# adc.net
KiCad netlist of a schematic drawn in Altium Designer
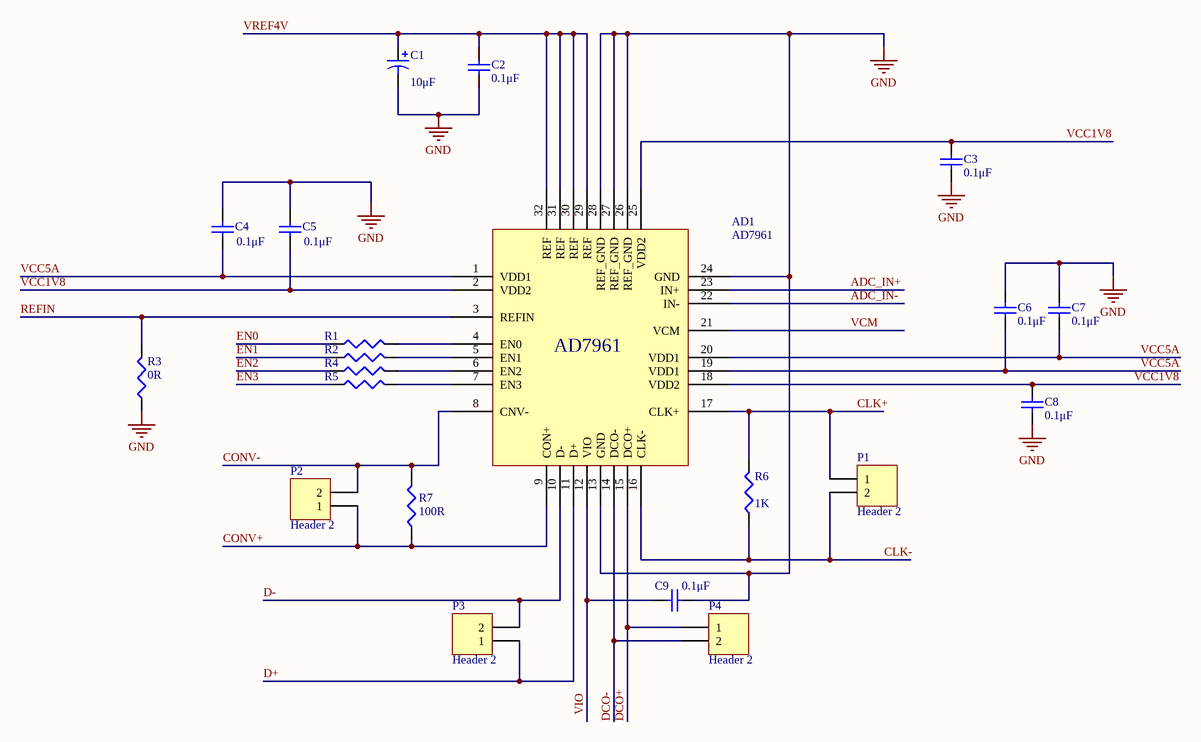
[diagram p0: adc.SchDoc]

(export (version "E")
  (design (tool "Eeschema 10.0.6"))
  (components
    (comp (ref "AD1")
      (value "AD7961")
      (footprint "QFN50P500X500X80-33N")
      (libsource (lib "nir_usb") (part "AD7961"))
    )
    (comp (ref "C1")
      (value "10μF")
      (footprint "C0805")
      (description "Polarized Capacitor (Surface Mount)")
      (fields (field (name "Comment") "Cap Pol3") (field (name "PUBLISHER") "Altium Limited"))
      (libsource (lib "Miscellaneous Devices") (part "Cap Pol3"))
    )
    (comp (ref "C2")
      (value "0.1μF")
      (footprint "1608[0603]")
      (description "Capacitor (Semiconductor SIM Model)")
      (fields (field (name "Comment") "Cap Semi") (field (name "PUBLISHER") "Altium Limited"))
      (libsource (lib "Miscellaneous Devices") (part "Cap Semi"))
    )
    (comp (ref "C3")
      (value "0.1μF")
      (footprint "1608[0603]")
      (description "Capacitor (Semiconductor SIM Model)")
      (fields (field (name "Comment") "Cap Semi") (field (name "PUBLISHER") "Altium Limited"))
      (libsource (lib "Miscellaneous Devices") (part "Cap Semi"))
    )
    (comp (ref "C4")
      (value "0.1μF")
      (footprint "1608[0603]")
      (description "Capacitor (Semiconductor SIM Model)")
      (fields (field (name "Comment") "Cap Semi") (field (name "PUBLISHER") "Altium Limited"))
      (libsource (lib "Miscellaneous Devices") (part "Cap Semi"))
    )
    (comp (ref "C5")
      (value "0.1μF")
      (footprint "1608[0603]")
      (description "Capacitor (Semiconductor SIM Model)")
      (fields (field (name "Comment") "Cap Semi") (field (name "PUBLISHER") "Altium Limited"))
      (libsource (lib "Miscellaneous Devices") (part "Cap Semi"))
    )
    (comp (ref "C6")
      (value "0.1μF")
      (footprint "1608[0603]")
      (description "Capacitor (Semiconductor SIM Model)")
      (fields (field (name "Comment") "Cap Semi") (field (name "PUBLISHER") "Altium Limited"))
      (libsource (lib "Miscellaneous Devices") (part "Cap Semi"))
    )
    (comp (ref "C7")
      (value "0.1μF")
      (footprint "1608[0603]")
      (description "Capacitor (Semiconductor SIM Model)")
      (fields (field (name "Comment") "Cap Semi") (field (name "PUBLISHER") "Altium Limited"))
      (libsource (lib "Miscellaneous Devices") (part "Cap Semi"))
    )
    (comp (ref "C8")
      (value "0.1μF")
      (footprint "1608[0603]")
      (description "Capacitor (Semiconductor SIM Model)")
      (fields (field (name "Comment") "Cap Semi") (field (name "PUBLISHER") "Altium Limited"))
      (libsource (lib "Miscellaneous Devices") (part "Cap Semi"))
    )
    (comp (ref "C9")
      (value "0.1μF")
      (footprint "1608[0603]")
      (description "Capacitor (Semiconductor SIM Model)")
      (fields (field (name "Comment") "Cap Semi") (field (name "PUBLISHER") "Altium Limited"))
      (libsource (lib "Miscellaneous Devices") (part "Cap Semi"))
    )
    (comp (ref "P1")
      (value "Header 2")
      (footprint "HDR1X2")
      (description "Header, 2-Pin")
      (fields (field (name "PUBLISHER") "Altium Limited"))
      (libsource (lib "Miscellaneous Connectors") (part "Header 2"))
    )
    (comp (ref "P2")
      (value "Header 2")
      (footprint "HDR1X2")
      (description "Header, 2-Pin")
      (fields (field (name "PUBLISHER") "Altium Limited"))
      (libsource (lib "") (part "Header 2_1"))
    )
    (comp (ref "P3")
      (value "Header 2")
      (footprint "HDR1X2")
      (description "Header, 2-Pin")
      (fields (field (name "PUBLISHER") "Altium Limited"))
      (libsource (lib "") (part "Header 2_1"))
    )
    (comp (ref "P4")
      (value "Header 2")
      (footprint "HDR1X2")
      (description "Header, 2-Pin")
      (fields (field (name "PUBLISHER") "Altium Limited"))
      (libsource (lib "Miscellaneous Connectors") (part "Header 2"))
    )
    (comp (ref "R1")
      (value "Res3")
      (footprint "J1-0603")
      (description "Resistor")
      (fields (field (name "PUBLISHER") "Altium Limited"))
      (libsource (lib "Miscellaneous Devices") (part "Res3"))
    )
    (comp (ref "R2")
      (value "Res3")
      (footprint "J1-0603")
      (description "Resistor")
      (fields (field (name "PUBLISHER") "Altium Limited"))
      (libsource (lib "Miscellaneous Devices") (part "Res3"))
    )
    (comp (ref "R3")
      (value "0R")
      (footprint "J1-0603")
      (description "Resistor")
      (fields (field (name "PUBLISHER") "Altium Limited"))
      (libsource (lib "Miscellaneous Devices") (part "Res3"))
    )
    (comp (ref "R4")
      (value "Res3")
      (footprint "J1-0603")
      (description "Resistor")
      (fields (field (name "PUBLISHER") "Altium Limited"))
      (libsource (lib "Miscellaneous Devices") (part "Res3"))
    )
    (comp (ref "R5")
      (value "Res3")
      (footprint "J1-0603")
      (description "Resistor")
      (fields (field (name "PUBLISHER") "Altium Limited"))
      (libsource (lib "Miscellaneous Devices") (part "Res3"))
    )
    (comp (ref "R6")
      (value "1K")
      (footprint "J1-0603")
      (description "Resistor")
      (fields (field (name "Comment") "Res3") (field (name "PUBLISHER") "Altium Limited"))
      (libsource (lib "Miscellaneous Devices") (part "Res3"))
    )
    (comp (ref "R7")
      (value "100R")
      (footprint "J1-0603")
      (description "Resistor")
      (fields (field (name "Comment") "Res3") (field (name "PUBLISHER") "Altium Limited"))
      (libsource (lib "Miscellaneous Devices") (part "Res3"))
    )
  )
  (nets
    (net (code "1") (name "/ADC_IN+") (class "Default")
      (node (ref "AD1") (pin "23") (pinfunction "IN+_23") (pintype "passive"))
    )
    (net (code "2") (name "/ADC_IN-") (class "Default")
      (node (ref "AD1") (pin "22") (pinfunction "IN-_22") (pintype "passive"))
    )
    (net (code "3") (name "/CLK+") (class "Default")
      (node (ref "AD1") (pin "17") (pinfunction "CLK+_17") (pintype "passive"))
      (node (ref "P1") (pin "1") (pinfunction "1_1") (pintype "passive"))
      (node (ref "R6") (pin "2") (pinfunction "2_2") (pintype "passive"))
    )
    (net (code "4") (name "/CLK-") (class "Default")
      (node (ref "AD1") (pin "16") (pinfunction "CLK-_16") (pintype "passive"))
      (node (ref "P1") (pin "2") (pinfunction "2_2") (pintype "passive"))
      (node (ref "R6") (pin "1") (pinfunction "1_1") (pintype "passive"))
    )
    (net (code "5") (name "/CONV+") (class "Default")
      (node (ref "AD1") (pin "9") (pinfunction "CON+_9") (pintype "passive"))
      (node (ref "P2") (pin "1") (pinfunction "1_1") (pintype "passive"))
      (node (ref "R7") (pin "1") (pinfunction "1_1") (pintype "passive"))
    )
    (net (code "6") (name "/CONV-") (class "Default")
      (node (ref "AD1") (pin "8") (pinfunction "CNV-_8") (pintype "passive"))
      (node (ref "P2") (pin "2") (pinfunction "2_2") (pintype "passive"))
      (node (ref "R7") (pin "2") (pinfunction "2_2") (pintype "passive"))
    )
    (net (code "7") (name "/D+") (class "Default")
      (node (ref "AD1") (pin "11") (pinfunction "D+_11") (pintype "passive"))
      (node (ref "P3") (pin "1") (pinfunction "1_1") (pintype "passive"))
    )
    (net (code "8") (name "/D-") (class "Default")
      (node (ref "AD1") (pin "10") (pinfunction "D-_10") (pintype "passive"))
      (node (ref "P3") (pin "2") (pinfunction "2_2") (pintype "passive"))
    )
    (net (code "9") (name "/DCO+") (class "Default")
      (node (ref "AD1") (pin "15") (pinfunction "DCO+_15") (pintype "passive"))
      (node (ref "P4") (pin "1") (pinfunction "1_1") (pintype "passive"))
    )
    (net (code "10") (name "/DCO-") (class "Default")
      (node (ref "AD1") (pin "14") (pinfunction "DCO-_14") (pintype "passive"))
      (node (ref "P4") (pin "2") (pinfunction "2_2") (pintype "passive"))
    )
    (net (code "11") (name "/EN0") (class "Default")
      (node (ref "R1") (pin "1") (pinfunction "1_1") (pintype "passive"))
    )
    (net (code "12") (name "/EN1") (class "Default")
      (node (ref "R2") (pin "1") (pinfunction "1_1") (pintype "passive"))
    )
    (net (code "13") (name "/EN2") (class "Default")
      (node (ref "R4") (pin "1") (pinfunction "1_1") (pintype "passive"))
    )
    (net (code "14") (name "/EN3") (class "Default")
      (node (ref "R5") (pin "1") (pinfunction "1_1") (pintype "passive"))
    )
    (net (code "15") (name "/REFIN") (class "Default")
      (node (ref "AD1") (pin "3") (pinfunction "REFIN_3") (pintype "passive"))
      (node (ref "R3") (pin "2") (pinfunction "2_2") (pintype "passive"))
    )
    (net (code "16") (name "/VCC1V8") (class "Default")
      (node (ref "AD1") (pin "18") (pinfunction "VDD2_18") (pintype "passive"))
      (node (ref "AD1") (pin "2") (pinfunction "VDD2_2") (pintype "passive"))
      (node (ref "AD1") (pin "25") (pinfunction "VDD2_25") (pintype "passive"))
      (node (ref "C3") (pin "1") (pinfunction "1_1") (pintype "passive"))
      (node (ref "C5") (pin "1") (pinfunction "1_1") (pintype "passive"))
      (node (ref "C8") (pin "1") (pinfunction "1_1") (pintype "passive"))
    )
    (net (code "17") (name "/VCC5A") (class "Default")
      (node (ref "AD1") (pin "1") (pinfunction "VDD1_1") (pintype "passive"))
      (node (ref "AD1") (pin "19") (pinfunction "VDD1_19") (pintype "passive"))
      (node (ref "AD1") (pin "20") (pinfunction "VDD1_20") (pintype "passive"))
      (node (ref "C4") (pin "1") (pinfunction "1_1") (pintype "passive"))
      (node (ref "C6") (pin "2") (pinfunction "2_2") (pintype "passive"))
      (node (ref "C7") (pin "2") (pinfunction "2_2") (pintype "passive"))
    )
    (net (code "18") (name "/VCM") (class "Default")
      (node (ref "AD1") (pin "21") (pinfunction "VCM_21") (pintype "passive"))
    )
    (net (code "19") (name "/VIO") (class "Default")
      (node (ref "AD1") (pin "12") (pinfunction "VIO_12") (pintype "passive"))
      (node (ref "C9") (pin "2") (pinfunction "2_2") (pintype "passive"))
    )
    (net (code "20") (name "/VREF4V") (class "Default")
      (node (ref "AD1") (pin "29") (pinfunction "REF_29") (pintype "passive"))
      (node (ref "AD1") (pin "30") (pinfunction "REF_30") (pintype "passive"))
      (node (ref "AD1") (pin "31") (pinfunction "REF_31") (pintype "passive"))
      (node (ref "AD1") (pin "32") (pinfunction "REF_32") (pintype "passive"))
      (node (ref "C1") (pin "1") (pinfunction "1_1") (pintype "passive"))
      (node (ref "C2") (pin "1") (pinfunction "1_1") (pintype "passive"))
    )
    (net (code "21") (name "GND") (class "Default")
      (node (ref "AD1") (pin "13") (pinfunction "GND_13") (pintype "passive"))
      (node (ref "AD1") (pin "24") (pinfunction "GND_24") (pintype "passive"))
      (node (ref "AD1") (pin "26") (pinfunction "REF_GND_26") (pintype "passive"))
      (node (ref "AD1") (pin "27") (pinfunction "REF_GND_27") (pintype "passive"))
      (node (ref "AD1") (pin "28") (pinfunction "REF_GND_28") (pintype "passive"))
      (node (ref "C1") (pin "2") (pinfunction "2_2") (pintype "passive"))
      (node (ref "C2") (pin "2") (pinfunction "2_2") (pintype "passive"))
      (node (ref "C3") (pin "2") (pinfunction "2_2") (pintype "passive"))
      (node (ref "C4") (pin "2") (pinfunction "2_2") (pintype "passive"))
      (node (ref "C5") (pin "2") (pinfunction "2_2") (pintype "passive"))
      (node (ref "C6") (pin "1") (pinfunction "1_1") (pintype "passive"))
      (node (ref "C7") (pin "1") (pinfunction "1_1") (pintype "passive"))
      (node (ref "C8") (pin "2") (pinfunction "2_2") (pintype "passive"))
      (node (ref "C9") (pin "1") (pinfunction "1_1") (pintype "passive"))
      (node (ref "R3") (pin "1") (pinfunction "1_1") (pintype "passive"))
    )
    (net (code "22") (name "Net-(AD1-EN0)") (class "Default")
      (node (ref "AD1") (pin "4") (pinfunction "EN0_4") (pintype "passive"))
      (node (ref "R1") (pin "2") (pinfunction "2_2") (pintype "passive"))
    )
    (net (code "23") (name "Net-(AD1-EN1)") (class "Default")
      (node (ref "AD1") (pin "5") (pinfunction "EN1_5") (pintype "passive"))
      (node (ref "R2") (pin "2") (pinfunction "2_2") (pintype "passive"))
    )
    (net (code "24") (name "Net-(AD1-EN2)") (class "Default")
      (node (ref "AD1") (pin "6") (pinfunction "EN2_6") (pintype "passive"))
      (node (ref "R4") (pin "2") (pinfunction "2_2") (pintype "passive"))
    )
    (net (code "25") (name "Net-(AD1-EN3)") (class "Default")
      (node (ref "AD1") (pin "7") (pinfunction "EN3_7") (pintype "passive"))
      (node (ref "R5") (pin "2") (pinfunction "2_2") (pintype "passive"))
    )
  )
)
